# UIAPduino_Pro_Micro.net
KiCad netlist of a schematic drawn in EAGLE
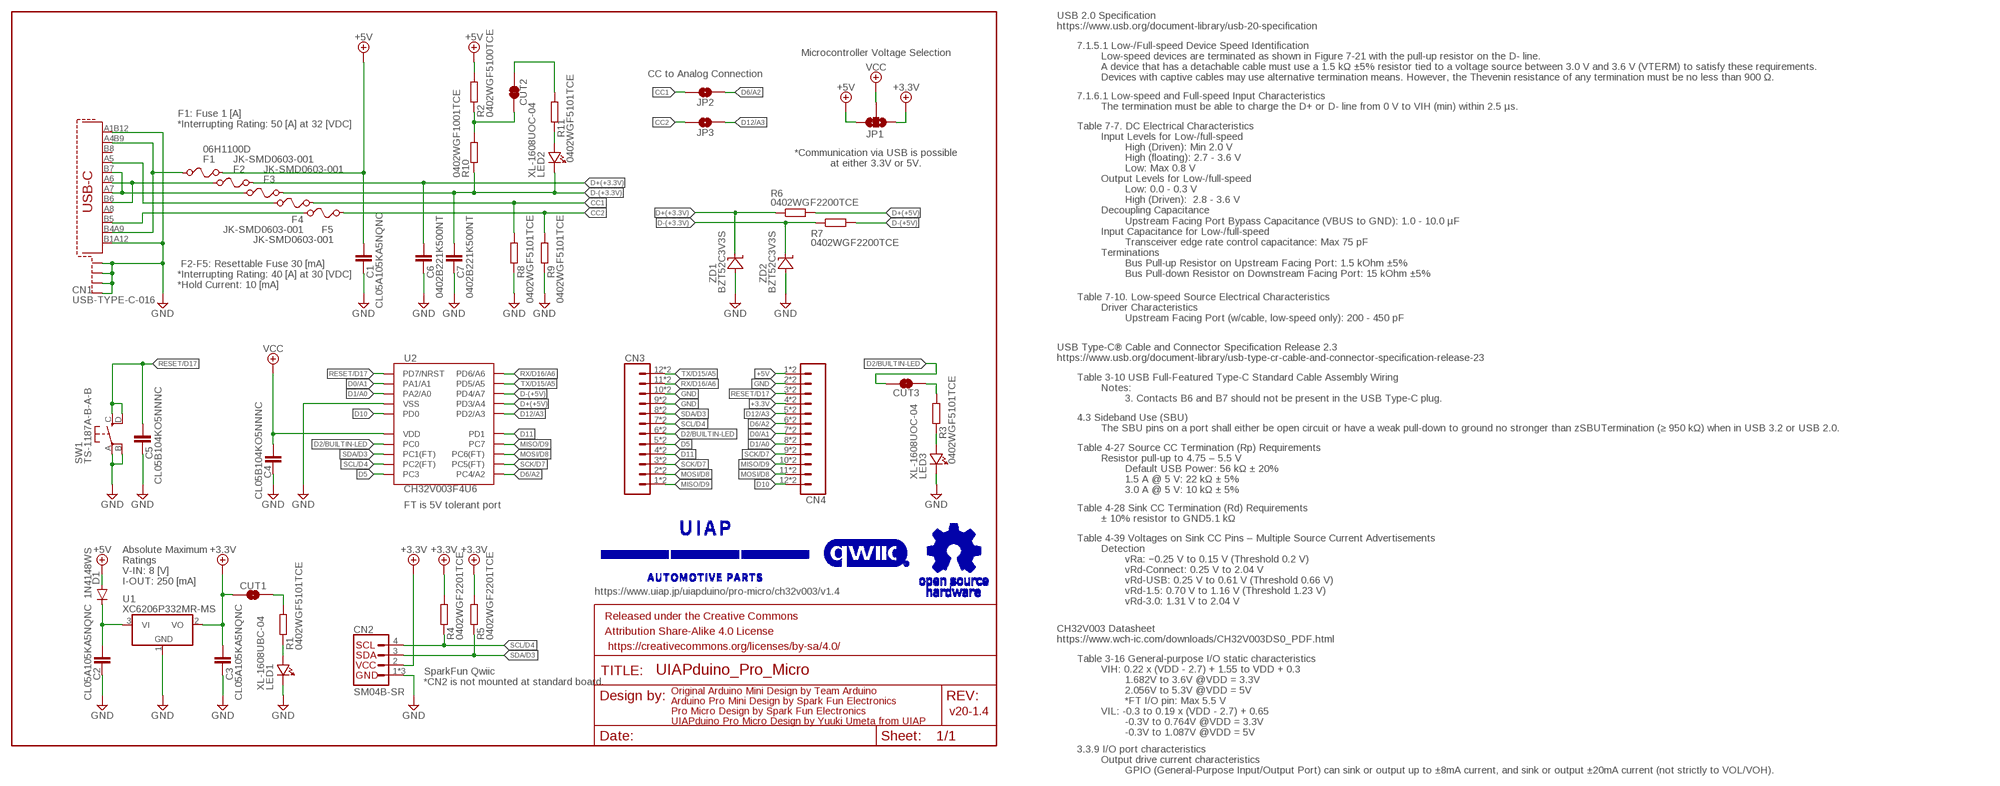
[diagram p0: schematic, sheet 1]

(export (version "E")
  (design (tool "Eeschema 10.0.6"))
  (components
    (comp (ref "C1")
      (value "CL05A105KA5NQNC")
      (footprint "eagle-import:1005")
      (libsource (lib "eagle-import") (part "C1005"))
    )
    (comp (ref "C2")
      (value "CL05A105KA5NQNC")
      (footprint "eagle-import:1005")
      (libsource (lib "eagle-import") (part "C1005"))
    )
    (comp (ref "C3")
      (value "CL05A105KA5NQNC")
      (footprint "eagle-import:1005")
      (libsource (lib "eagle-import") (part "C1005"))
    )
    (comp (ref "C4")
      (value "CL05B104KO5NNNC")
      (footprint "eagle-import:1005")
      (libsource (lib "eagle-import") (part "C1005"))
    )
    (comp (ref "C5")
      (value "CL05B104KO5NNNC")
      (footprint "eagle-import:1005")
      (libsource (lib "eagle-import") (part "C1005"))
    )
    (comp (ref "C6")
      (value "0402B221K500NT")
      (footprint "eagle-import:1005")
      (libsource (lib "eagle-import") (part "C1005"))
    )
    (comp (ref "C7")
      (value "0402B221K500NT")
      (footprint "eagle-import:1005")
      (libsource (lib "eagle-import") (part "C1005"))
    )
    (comp (ref "CN1")
      (value "USB-TYPE-C-016")
      (footprint "eagle-import:USB-TYPE-C-016")
      (libsource (lib "eagle-import") (part "USB-TYPE-C-016"))
    )
    (comp (ref "CN2")
      (value "SM04B-SR")
      (footprint "eagle-import:JST04_1MM_RA")
      (libsource (lib "eagle-import") (part "QWIIC_CONNECTORJS-1MM-GND"))
    )
    (comp (ref "CN3")
      (value "CONN_12CASTLE_0.9MM")
      (footprint "eagle-import:1X12_CASTELLATED_0.9MM")
      (libsource (lib "eagle-import") (part "CONN_12CASTLE_0.9MM"))
    )
    (comp (ref "CN4")
      (value "CONN_12CASTLE_0.9MM")
      (footprint "eagle-import:1X12_CASTELLATED_0.9MM")
      (libsource (lib "eagle-import") (part "CONN_12CASTLE_0.9MM"))
    )
    (comp (ref "CUT1")
      (value "SMT-JP-2-NC")
      (footprint "eagle-import:SMT-JUMPER_2_NC_SILK_ROUND")
      (libsource (lib "eagle-import") (part "SMT-JP-2-NC"))
    )
    (comp (ref "CUT2")
      (value "SMT-JP-2-NC")
      (footprint "eagle-import:SMT-JUMPER_2_NC_SILK_ROUND")
      (libsource (lib "eagle-import") (part "SMT-JP-2-NC"))
    )
    (comp (ref "CUT3")
      (value "SMT-JP-2-NC")
      (footprint "eagle-import:SMT-JUMPER_2_NC_SILK_ROUND")
      (libsource (lib "eagle-import") (part "SMT-JP-2-NC"))
    )
    (comp (ref "D1")
      (value "1N4148WS")
      (footprint "eagle-import:SOD323-R")
      (libsource (lib "eagle-import") (part "DIODE-SOD323-R"))
    )
    (comp (ref "F1")
      (value "06H1100D")
      (footprint "eagle-import:1608")
      (libsource (lib "eagle-import") (part "06H1100D"))
    )
    (comp (ref "F2")
      (value "JK-SMD0603-001")
      (footprint "eagle-import:1608")
      (libsource (lib "eagle-import") (part "06H1100D"))
    )
    (comp (ref "F3")
      (value "JK-SMD0603-001")
      (footprint "eagle-import:1608")
      (libsource (lib "eagle-import") (part "06H1100D"))
    )
    (comp (ref "F4")
      (value "JK-SMD0603-001")
      (footprint "eagle-import:1608")
      (libsource (lib "eagle-import") (part "06H1100D"))
    )
    (comp (ref "F5")
      (value "JK-SMD0603-001")
      (footprint "eagle-import:1608")
      (libsource (lib "eagle-import") (part "06H1100D"))
    )
    (comp (ref "FRAME1")
      (value "FRAME-LETTER")
      (footprint "eagle-import:CREATIVE_COMMONS")
      (libsource (lib "eagle-import") (part "FRAME-LETTER"))
    )
    (comp (ref "JP1")
      (value "SMT-JP-3-NO-NC")
      (footprint "eagle-import:SMT-JUMPER_3_1-NC_TRACE_SILK")
      (libsource (lib "eagle-import") (part "SMT-JP-3-NO-NC"))
    )
    (comp (ref "JP2")
      (value "SMT-JP-2-NO")
      (footprint "eagle-import:SMT-JUMPER_2_NO_SILK_ROUND")
      (libsource (lib "eagle-import") (part "SMT-JP-2-NO"))
    )
    (comp (ref "JP3")
      (value "SMT-JP-2-NO")
      (footprint "eagle-import:SMT-JUMPER_2_NO_SILK_ROUND")
      (libsource (lib "eagle-import") (part "SMT-JP-2-NO"))
    )
    (comp (ref "LED1")
      (value "XL-1608UBC-04")
      (footprint "eagle-import:1608-LED")
      (libsource (lib "eagle-import") (part "XL-1608UBC-04"))
    )
    (comp (ref "LED2")
      (value "XL-1608UOC-04")
      (footprint "eagle-import:1608-LED")
      (libsource (lib "eagle-import") (part "XL-1608UOC-04"))
    )
    (comp (ref "LED3")
      (value "XL-1608UOC-04")
      (footprint "eagle-import:1608-LED")
      (libsource (lib "eagle-import") (part "XL-1608UOC-04"))
    )
    (comp (ref "R1")
      (value "0402WGF5101TCE")
      (footprint "eagle-import:1005")
      (libsource (lib "eagle-import") (part "R1005"))
    )
    (comp (ref "R2")
      (value "0402WGF5100TCE")
      (footprint "eagle-import:1005")
      (libsource (lib "eagle-import") (part "R1005"))
    )
    (comp (ref "R3")
      (value "0402WGF5101TCE")
      (footprint "eagle-import:1005")
      (libsource (lib "eagle-import") (part "R1005"))
    )
    (comp (ref "R4")
      (value "0402WGF2201TCE")
      (footprint "eagle-import:1005")
      (libsource (lib "eagle-import") (part "R1005"))
    )
    (comp (ref "R5")
      (value "0402WGF2201TCE")
      (footprint "eagle-import:1005")
      (libsource (lib "eagle-import") (part "R1005"))
    )
    (comp (ref "R6")
      (value "0402WGF2200TCE")
      (footprint "eagle-import:1005")
      (libsource (lib "eagle-import") (part "R1005"))
    )
    (comp (ref "R7")
      (value "0402WGF2200TCE")
      (footprint "eagle-import:1005")
      (libsource (lib "eagle-import") (part "R1005"))
    )
    (comp (ref "R8")
      (value "0402WGF5101TCE")
      (footprint "eagle-import:1005")
      (libsource (lib "eagle-import") (part "R1005"))
    )
    (comp (ref "R9")
      (value "0402WGF5101TCE")
      (footprint "eagle-import:1005")
      (libsource (lib "eagle-import") (part "R1005"))
    )
    (comp (ref "R10")
      (value "0402WGF1001TCE")
      (footprint "eagle-import:1005")
      (libsource (lib "eagle-import") (part "R1005"))
    )
    (comp (ref "R11")
      (value "0402WGF5101TCE")
      (footprint "eagle-import:1005")
      (libsource (lib "eagle-import") (part "R1005"))
    )
    (comp (ref "SW1")
      (value "TS-1187A-B-A-B")
      (footprint "eagle-import:TS-1187A-B-A-B")
      (libsource (lib "eagle-import") (part "TS-1187A-B-A-B"))
    )
    (comp (ref "U1")
      (value "XC6206P332MR-MS")
      (footprint "eagle-import:SOT-23F_TOS")
      (libsource (lib "eagle-import") (part "XC6206P332MR-MS"))
    )
    (comp (ref "U2")
      (value "CH32V003F4U6")
      (footprint "eagle-import:QFN40P300X300X100-21T110")
      (libsource (lib "eagle-import") (part "CH32V003F4U6"))
    )
    (comp (ref "ZD1")
      (value "BZT52C3V3S")
      (footprint "eagle-import:SOD323-R")
      (libsource (lib "eagle-import") (part "BZT52C3V3S"))
    )
    (comp (ref "ZD2")
      (value "BZT52C3V3S")
      (footprint "eagle-import:SOD323-R")
      (libsource (lib "eagle-import") (part "BZT52C3V3S"))
    )
  )
  (nets
    (net (code "1") (name "+3.3V") (class "Default")
      (node (ref "C3") (pin "1") (pinfunction "1_1") (pintype "passive"))
      (node (ref "CN2") (pin "2") (pinfunction "2_2") (pintype "power_in"))
      (node (ref "CN4") (pin "4") (pinfunction "4_4") (pintype "passive"))
      (node (ref "CN4") (pin "4B") (pinfunction "4_4B") (pintype "passive"))
      (node (ref "CUT1") (pin "2") (pinfunction "2_2") (pintype "passive"))
      (node (ref "JP1") (pin "1") (pinfunction "1_1") (pintype "passive"))
      (node (ref "R4") (pin "2") (pinfunction "2_2") (pintype "passive"))
      (node (ref "R5") (pin "2") (pinfunction "2_2") (pintype "passive"))
      (node (ref "U1") (pin "2") (pinfunction "VO_2") (pintype "passive"))
    )
    (net (code "2") (name "+5V") (class "Default")
      (node (ref "C1") (pin "1") (pinfunction "1_1") (pintype "passive"))
      (node (ref "CN4") (pin "1") (pinfunction "1_1") (pintype "passive"))
      (node (ref "CN4") (pin "1B") (pinfunction "1_1B") (pintype "passive"))
      (node (ref "D1") (pin "A") (pinfunction "A_A") (pintype "passive"))
      (node (ref "F1") (pin "2") (pinfunction "2_2") (pintype "passive"))
      (node (ref "JP1") (pin "3") (pinfunction "3_3") (pintype "passive"))
      (node (ref "R2") (pin "2") (pinfunction "2_2") (pintype "passive"))
    )
    (net (code "3") (name "CC1") (class "Default")
      (node (ref "F4") (pin "2") (pinfunction "2_2") (pintype "passive"))
      (node (ref "JP2") (pin "1") (pinfunction "1_1") (pintype "passive"))
      (node (ref "R8") (pin "2") (pinfunction "2_2") (pintype "passive"))
    )
    (net (code "4") (name "CC2") (class "Default")
      (node (ref "F5") (pin "2") (pinfunction "2_2") (pintype "passive"))
      (node (ref "JP3") (pin "1") (pinfunction "1_1") (pintype "passive"))
      (node (ref "R9") (pin "2") (pinfunction "2_2") (pintype "passive"))
    )
    (net (code "5") (name "D+(+3.3V)") (class "Default")
      (node (ref "C6") (pin "1") (pinfunction "1_1") (pintype "passive"))
      (node (ref "F2") (pin "2") (pinfunction "2_2") (pintype "passive"))
      (node (ref "R6") (pin "1") (pinfunction "1_1") (pintype "passive"))
      (node (ref "ZD1") (pin "C") (pinfunction "C_C") (pintype "passive"))
    )
    (net (code "6") (name "D+(+5V)") (class "Default")
      (node (ref "R6") (pin "2") (pinfunction "2_2") (pintype "passive"))
      (node (ref "U2") (pin "17") (pinfunction "PD3/A4_17") (pintype "bidirectional"))
    )
    (net (code "7") (name "D-(+3.3V)") (class "Default")
      (node (ref "C7") (pin "1") (pinfunction "1_1") (pintype "passive"))
      (node (ref "F3") (pin "2") (pinfunction "2_2") (pintype "passive"))
      (node (ref "LED2") (pin "2") (pinfunction "C_2") (pintype "passive"))
      (node (ref "R10") (pin "1") (pinfunction "1_1") (pintype "passive"))
      (node (ref "R7") (pin "1") (pinfunction "1_1") (pintype "passive"))
      (node (ref "ZD2") (pin "C") (pinfunction "C_C") (pintype "passive"))
    )
    (net (code "8") (name "D-(+5V)") (class "Default")
      (node (ref "R7") (pin "2") (pinfunction "2_2") (pintype "passive"))
      (node (ref "U2") (pin "18") (pinfunction "PD4/A7_18") (pintype "bidirectional"))
    )
    (net (code "9") (name "D0{slash}A1") (class "Default")
      (node (ref "CN4") (pin "7") (pinfunction "7_7") (pintype "passive"))
      (node (ref "CN4") (pin "7B") (pinfunction "7_7B") (pintype "passive"))
      (node (ref "U2") (pin "2") (pinfunction "PA1/A1_2") (pintype "bidirectional"))
    )
    (net (code "10") (name "D1{slash}A0") (class "Default")
      (node (ref "CN4") (pin "8") (pinfunction "8_8") (pintype "passive"))
      (node (ref "CN4") (pin "8B") (pinfunction "8_8B") (pintype "passive"))
      (node (ref "U2") (pin "3") (pinfunction "PA2/A0_3") (pintype "bidirectional"))
    )
    (net (code "11") (name "D2{slash}BUILTIN-LED") (class "Default")
      (node (ref "CN3") (pin "6") (pinfunction "6_6") (pintype "passive"))
      (node (ref "CN3") (pin "6B") (pinfunction "6_6B") (pintype "passive"))
      (node (ref "CUT3") (pin "1") (pinfunction "1_1") (pintype "passive"))
      (node (ref "U2") (pin "7") (pinfunction "PC0_7") (pintype "bidirectional"))
    )
    (net (code "12") (name "D5") (class "Default")
      (node (ref "CN3") (pin "5") (pinfunction "5_5") (pintype "passive"))
      (node (ref "CN3") (pin "5B") (pinfunction "5_5B") (pintype "passive"))
      (node (ref "U2") (pin "10") (pinfunction "PC3_10") (pintype "bidirectional"))
    )
    (net (code "13") (name "D6{slash}A2") (class "Default")
      (node (ref "CN4") (pin "6") (pinfunction "6_6") (pintype "passive"))
      (node (ref "CN4") (pin "6B") (pinfunction "6_6B") (pintype "passive"))
      (node (ref "JP2") (pin "2") (pinfunction "2_2") (pintype "passive"))
      (node (ref "U2") (pin "11") (pinfunction "PC4/A2_11") (pintype "bidirectional"))
    )
    (net (code "14") (name "D10") (class "Default")
      (node (ref "CN4") (pin "12") (pinfunction "12_12") (pintype "passive"))
      (node (ref "CN4") (pin "12B") (pinfunction "12_12B") (pintype "passive"))
      (node (ref "U2") (pin "5") (pinfunction "PD0_5") (pintype "bidirectional"))
    )
    (net (code "15") (name "D11") (class "Default")
      (node (ref "CN3") (pin "4") (pinfunction "4_4") (pintype "passive"))
      (node (ref "CN3") (pin "4B") (pinfunction "4_4B") (pintype "passive"))
      (node (ref "U2") (pin "15") (pinfunction "PD1_15") (pintype "bidirectional"))
    )
    (net (code "16") (name "D12{slash}A3") (class "Default")
      (node (ref "CN4") (pin "5") (pinfunction "5_5") (pintype "passive"))
      (node (ref "CN4") (pin "5B") (pinfunction "5_5B") (pintype "passive"))
      (node (ref "JP3") (pin "2") (pinfunction "2_2") (pintype "passive"))
      (node (ref "U2") (pin "16") (pinfunction "PD2/A3_16") (pintype "bidirectional"))
    )
    (net (code "17") (name "GND") (class "Default")
      (node (ref "C1") (pin "2") (pinfunction "2_2") (pintype "passive"))
      (node (ref "C2") (pin "2") (pinfunction "2_2") (pintype "passive"))
      (node (ref "C3") (pin "2") (pinfunction "2_2") (pintype "passive"))
      (node (ref "C4") (pin "2") (pinfunction "2_2") (pintype "passive"))
      (node (ref "C5") (pin "2") (pinfunction "2_2") (pintype "passive"))
      (node (ref "C6") (pin "2") (pinfunction "2_2") (pintype "passive"))
      (node (ref "C7") (pin "2") (pinfunction "2_2") (pintype "passive"))
      (node (ref "CN1") (pin "A1B12") (pinfunction "GND_A1B12") (pintype "power_in"))
      (node (ref "CN1") (pin "B1A12") (pinfunction "GND_B1A12") (pintype "power_in"))
      (node (ref "CN1") (pin "S1") (pinfunction "S1_S1") (pintype "passive"))
      (node (ref "CN1") (pin "S1B") (pinfunction "S1_S1B") (pintype "passive"))
      (node (ref "CN1") (pin "S2") (pinfunction "S2_S2") (pintype "passive"))
      (node (ref "CN1") (pin "S2B") (pinfunction "S2_S2B") (pintype "passive"))
      (node (ref "CN1") (pin "S3") (pinfunction "S3_S3") (pintype "passive"))
      (node (ref "CN1") (pin "S3B") (pinfunction "S3_S3B") (pintype "passive"))
      (node (ref "CN1") (pin "S4") (pinfunction "S4_S4") (pintype "passive"))
      (node (ref "CN1") (pin "S4B") (pinfunction "S4_S4B") (pintype "passive"))
      (node (ref "CN2") (pin "1") (pinfunction "1_1") (pintype "power_in"))
      (node (ref "CN2") (pin "NC1") (pinfunction "1_NC1") (pintype "power_in"))
      (node (ref "CN2") (pin "NC2") (pinfunction "1_NC2") (pintype "power_in"))
      (node (ref "CN3") (pin "10") (pinfunction "10_10") (pintype "passive"))
      (node (ref "CN3") (pin "10B") (pinfunction "10_10B") (pintype "passive"))
      (node (ref "CN3") (pin "9") (pinfunction "9_9") (pintype "passive"))
      (node (ref "CN3") (pin "9B") (pinfunction "9_9B") (pintype "passive"))
      (node (ref "CN4") (pin "2") (pinfunction "2_2") (pintype "passive"))
      (node (ref "CN4") (pin "2B") (pinfunction "2_2B") (pintype "passive"))
      (node (ref "LED1") (pin "2") (pinfunction "C_2") (pintype "passive"))
      (node (ref "LED3") (pin "2") (pinfunction "C_2") (pintype "passive"))
      (node (ref "R8") (pin "1") (pinfunction "1_1") (pintype "passive"))
      (node (ref "R9") (pin "1") (pinfunction "1_1") (pintype "passive"))
      (node (ref "SW1") (pin "A") (pinfunction "P_A") (pintype "passive"))
      (node (ref "SW1") (pin "B") (pinfunction "P1_B") (pintype "passive"))
      (node (ref "U1") (pin "1") (pinfunction "GND_1") (pintype "passive"))
      (node (ref "U2") (pin "21") (pinfunction "VSS_21") (pintype "power_in"))
      (node (ref "U2") (pin "4") (pinfunction "VSS_4") (pintype "power_in"))
      (node (ref "ZD1") (pin "A") (pinfunction "A_A") (pintype "passive"))
      (node (ref "ZD2") (pin "A") (pinfunction "A_A") (pintype "passive"))
    )
    (net (code "18") (name "MISO{slash}D9") (class "Default")
      (node (ref "CN3") (pin "1") (pinfunction "1_1") (pintype "passive"))
      (node (ref "CN3") (pin "1B") (pinfunction "1_1B") (pintype "passive"))
      (node (ref "CN4") (pin "10") (pinfunction "10_10") (pintype "passive"))
      (node (ref "CN4") (pin "10B") (pinfunction "10_10B") (pintype "passive"))
      (node (ref "U2") (pin "14") (pinfunction "PC7_14") (pintype "bidirectional"))
    )
    (net (code "19") (name "MOSI{slash}D8") (class "Default")
      (node (ref "CN3") (pin "2") (pinfunction "2_2") (pintype "passive"))
      (node (ref "CN3") (pin "2B") (pinfunction "2_2B") (pintype "passive"))
      (node (ref "CN4") (pin "11") (pinfunction "11_11") (pintype "passive"))
      (node (ref "CN4") (pin "11B") (pinfunction "11_11B") (pintype "passive"))
      (node (ref "U2") (pin "13") (pinfunction "PC6(FT)_13") (pintype "bidirectional"))
    )
    (net (code "20") (name "Net-(CN1-CC1)") (class "Default")
      (node (ref "CN1") (pin "A5") (pinfunction "CC1_A5") (pintype "passive"))
      (node (ref "F4") (pin "1") (pinfunction "1_1") (pintype "passive"))
    )
    (net (code "21") (name "Net-(CN1-CC2)") (class "Default")
      (node (ref "CN1") (pin "B5") (pinfunction "CC2_B5") (pintype "passive"))
      (node (ref "F5") (pin "1") (pinfunction "1_1") (pintype "passive"))
    )
    (net (code "22") (name "Net-(CN1-DN1)") (class "Default")
      (node (ref "CN1") (pin "A7") (pinfunction "DN1_A7") (pintype "passive"))
      (node (ref "CN1") (pin "B7") (pinfunction "DN2_B7") (pintype "passive"))
      (node (ref "F3") (pin "1") (pinfunction "1_1") (pintype "passive"))
    )
    (net (code "23") (name "Net-(CN1-DP1)") (class "Default")
      (node (ref "CN1") (pin "A6") (pinfunction "DP1_A6") (pintype "passive"))
      (node (ref "CN1") (pin "B6") (pinfunction "DP2_B6") (pintype "passive"))
      (node (ref "F2") (pin "1") (pinfunction "1_1") (pintype "passive"))
    )
    (net (code "24") (name "Net-(CN1-VBUS-PadA4B9)") (class "Default")
      (node (ref "CN1") (pin "A4B9") (pinfunction "VBUS_A4B9") (pintype "power_in"))
      (node (ref "CN1") (pin "B4A9") (pinfunction "VBUS_B4A9") (pintype "power_in"))
      (node (ref "F1") (pin "1") (pinfunction "1_1") (pintype "passive"))
    )
    (net (code "25") (name "Net-(CUT1-Pad1)") (class "Default")
      (node (ref "CUT1") (pin "1") (pinfunction "1_1") (pintype "passive"))
      (node (ref "R1") (pin "2") (pinfunction "2_2") (pintype "passive"))
    )
    (net (code "26") (name "Net-(CUT2-Pad1)") (class "Default")
      (node (ref "CUT2") (pin "1") (pinfunction "1_1") (pintype "passive"))
      (node (ref "R11") (pin "2") (pinfunction "2_2") (pintype "passive"))
    )
    (net (code "27") (name "Net-(CUT2-Pad2)") (class "Default")
      (node (ref "CUT2") (pin "2") (pinfunction "2_2") (pintype "passive"))
      (node (ref "R10") (pin "2") (pinfunction "2_2") (pintype "passive"))
      (node (ref "R2") (pin "1") (pinfunction "1_1") (pintype "passive"))
    )
    (net (code "28") (name "Net-(CUT3-Pad2)") (class "Default")
      (node (ref "CUT3") (pin "2") (pinfunction "2_2") (pintype "passive"))
      (node (ref "R3") (pin "2") (pinfunction "2_2") (pintype "passive"))
    )
    (net (code "29") (name "Net-(LED1-A)") (class "Default")
      (node (ref "LED1") (pin "1") (pinfunction "A_1") (pintype "passive"))
      (node (ref "R1") (pin "1") (pinfunction "1_1") (pintype "passive"))
    )
    (net (code "30") (name "Net-(LED2-A)") (class "Default")
      (node (ref "LED2") (pin "1") (pinfunction "A_1") (pintype "passive"))
      (node (ref "R11") (pin "1") (pinfunction "1_1") (pintype "passive"))
    )
    (net (code "31") (name "Net-(LED3-A)") (class "Default")
      (node (ref "LED3") (pin "1") (pinfunction "A_1") (pintype "passive"))
      (node (ref "R3") (pin "1") (pinfunction "1_1") (pintype "passive"))
    )
    (net (code "32") (name "Net-(U1-VI)") (class "Default")
      (node (ref "C2") (pin "1") (pinfunction "1_1") (pintype "passive"))
      (node (ref "D1") (pin "C") (pinfunction "C_C") (pintype "passive"))
      (node (ref "U1") (pin "3") (pinfunction "VI_3") (pintype "input"))
    )
    (net (code "33") (name "RESET{slash}D17") (class "Default")
      (node (ref "C5") (pin "1") (pinfunction "1_1") (pintype "passive"))
      (node (ref "CN4") (pin "3") (pinfunction "3_3") (pintype "passive"))
      (node (ref "CN4") (pin "3B") (pinfunction "3_3B") (pintype "passive"))
      (node (ref "SW1") (pin "C") (pinfunction "S_C") (pintype "passive"))
      (node (ref "SW1") (pin "D") (pinfunction "S1_D") (pintype "passive"))
      (node (ref "U2") (pin "1") (pinfunction "PD7/NRST_1") (pintype "bidirectional"))
    )
    (net (code "34") (name "RX{slash}D16{slash}A6") (class "Default")
      (node (ref "CN3") (pin "11") (pinfunction "11_11") (pintype "passive"))
      (node (ref "CN3") (pin "11B") (pinfunction "11_11B") (pintype "passive"))
      (node (ref "U2") (pin "20") (pinfunction "PD6/A6_20") (pintype "bidirectional"))
    )
    (net (code "35") (name "SCK{slash}D7") (class "Default")
      (node (ref "CN3") (pin "3") (pinfunction "3_3") (pintype "passive"))
      (node (ref "CN3") (pin "3B") (pinfunction "3_3B") (pintype "passive"))
      (node (ref "CN4") (pin "9") (pinfunction "9_9") (pintype "passive"))
      (node (ref "CN4") (pin "9B") (pinfunction "9_9B") (pintype "passive"))
      (node (ref "U2") (pin "12") (pinfunction "PC5(FT)_12") (pintype "bidirectional"))
    )
    (net (code "36") (name "SCL{slash}D4") (class "Default")
      (node (ref "CN2") (pin "4") (pinfunction "4_4") (pintype "passive"))
      (node (ref "CN3") (pin "7") (pinfunction "7_7") (pintype "passive"))
      (node (ref "CN3") (pin "7B") (pinfunction "7_7B") (pintype "passive"))
      (node (ref "R4") (pin "1") (pinfunction "1_1") (pintype "passive"))
      (node (ref "U2") (pin "9") (pinfunction "PC2(FT)_9") (pintype "bidirectional"))
    )
    (net (code "37") (name "SDA{slash}D3") (class "Default")
      (node (ref "CN2") (pin "3") (pinfunction "3_3") (pintype "passive"))
      (node (ref "CN3") (pin "8") (pinfunction "8_8") (pintype "passive"))
      (node (ref "CN3") (pin "8B") (pinfunction "8_8B") (pintype "passive"))
      (node (ref "R5") (pin "1") (pinfunction "1_1") (pintype "passive"))
      (node (ref "U2") (pin "8") (pinfunction "PC1(FT)_8") (pintype "bidirectional"))
    )
    (net (code "38") (name "TX{slash}D15{slash}A5") (class "Default")
      (node (ref "CN3") (pin "12") (pinfunction "12_12") (pintype "passive"))
      (node (ref "CN3") (pin "12B") (pinfunction "12_12B") (pintype "passive"))
      (node (ref "U2") (pin "19") (pinfunction "PD5/A5_19") (pintype "bidirectional"))
    )
    (net (code "39") (name "VCC") (class "Default")
      (node (ref "C4") (pin "1") (pinfunction "1_1") (pintype "passive"))
      (node (ref "JP1") (pin "2") (pinfunction "2_2") (pintype "passive"))
      (node (ref "U2") (pin "6") (pinfunction "VDD_6") (pintype "power_in"))
    )
    (net (code "40") (name "unconnected-(CN1-SBU1-PadA8)") (class "Default")
      (node (ref "CN1") (pin "A8") (pinfunction "SBU1_A8") (pintype "passive"))
    )
    (net (code "41") (name "unconnected-(CN1-SBU2-PadB8)") (class "Default")
      (node (ref "CN1") (pin "B8") (pinfunction "SBU2_B8") (pintype "passive"))
    )
  )
)
